# version_1.net
KiCad netlist of a schematic drawn in Altium Designer
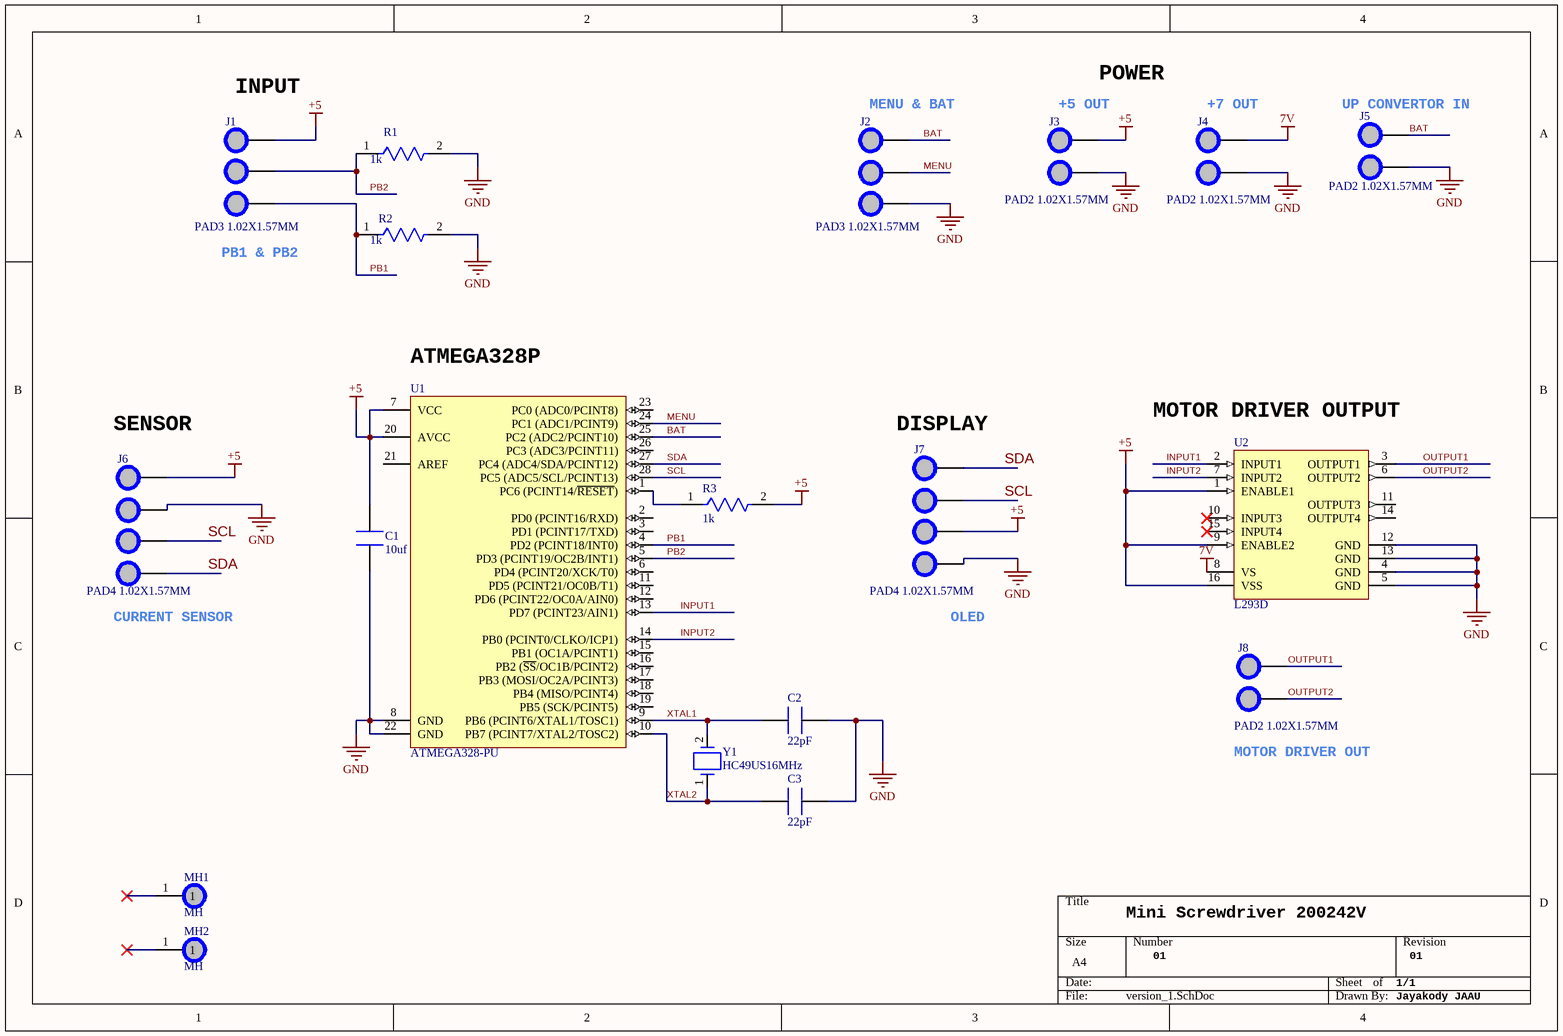
[diagram p0: version_1.SchDoc]

(export (version "E")
  (design (tool "Eeschema 10.0.6"))
  (components
    (comp (ref "C1")
      (value "10uf")
      (footprint "0805 cap")
      (fields
        (field (name "MANUFACTURER") "Samsung")
        (field (name "MANUFACTURER PART NUMBER") "CL21A106KOQNNNE")
        (field (name "TOLERANCE") "10%")
      )
      (libsource (lib "Schlib1") (part "CL21A106KOQNNNE"))
    )
    (comp (ref "C2")
      (value "22pF")
      (footprint "Capacitor_22pF")
      (description "Cap Ceramic Suppression X1/Y2 22pF 760VAC/500VAC U2J 10% (8 X 5mm) Radial 10mm 125C Bulk")
      (fields
        (field (name "MANUFACTURER") "Vishay BCcomponents")
        (field (name "MANUFACTURER PART NUMBER") "VY1220K31U2JQ63V0")
      )
      (libsource (lib "Schlib1") (part "VY1220K31U2JQ63V0"))
    )
    (comp (ref "C3")
      (value "22pF")
      (footprint "Capacitor_22pF")
      (description "Cap Ceramic Suppression X1/Y2 22pF 760VAC/500VAC U2J 10% (8 X 5mm) Radial 10mm 125C Bulk")
      (fields
        (field (name "MANUFACTURER") "Vishay BCcomponents")
        (field (name "MANUFACTURER PART NUMBER") "VY1220K31U2JQ63V0")
      )
      (libsource (lib "Schlib1") (part "VY1220K31U2JQ63V0"))
    )
    (comp (ref "J1")
      (value "PAD3 1.02X1.57MM")
      (footprint "PAD3 1.02X1.57MM")
      (libsource (lib "Schlib1") (part "PAD3 1.02X1.57MM"))
    )
    (comp (ref "J2")
      (value "PAD3 1.02X1.57MM")
      (footprint "PAD3 1.02X1.57MM")
      (libsource (lib "Schlib1") (part "PAD3 1.02X1.57MM"))
    )
    (comp (ref "J3")
      (value "PAD2 1.02X1.57MM")
      (footprint "PAD2 1.02X1.57MM")
      (libsource (lib "Schlib1") (part "PAD2 1.02X1.57MM"))
    )
    (comp (ref "J4")
      (value "PAD2 1.02X1.57MM")
      (footprint "PAD2 1.02X1.57MM")
      (libsource (lib "Schlib1") (part "PAD2 1.02X1.57MM"))
    )
    (comp (ref "J5")
      (value "PAD2 1.02X1.57MM")
      (footprint "PAD2 1.02X1.57MM")
      (libsource (lib "Schlib1") (part "PAD2 1.02X1.57MM"))
    )
    (comp (ref "J6")
      (value "PAD4 1.02X1.57MM")
      (footprint "PAD4 1.02X1.57MM")
      (libsource (lib "Schlib1") (part "PAD4 1.02X1.57MM"))
    )
    (comp (ref "J7")
      (value "PAD4 1.02X1.57MM")
      (footprint "PAD4 1.02X1.57MM")
      (libsource (lib "Schlib1") (part "PAD4 1.02X1.57MM"))
    )
    (comp (ref "J8")
      (value "PAD2 1.02X1.57MM")
      (footprint "PAD2 1.02X1.57MM")
      (libsource (lib "Schlib1") (part "PAD2 1.02X1.57MM"))
    )
    (comp (ref "MH1") (value "MH") (footprint "MH") (libsource (lib "Schlib1") (part "MH")))
    (comp (ref "MH2") (value "MH") (footprint "MH") (libsource (lib "Schlib1") (part "MH")))
    (comp (ref "R1")
      (value "1k")
      (footprint "resistor")
      (description "MRS25 Series Axial Thin Film Resistor 1kOhms +/-1% 0.6W +/-50ppm/degC")
      (fields
        (field (name "MANUFACTURER") "Vishay")
        (field (name "MANUFACTURER PART NUMBER") "MRS25000C1001FCT00")
      )
      (libsource (lib "Schlib1") (part "MRS25000C1001FCT00"))
    )
    (comp (ref "R2")
      (value "1k")
      (footprint "resistor")
      (description "MRS25 Series Axial Thin Film Resistor 1kOhms +/-1% 0.6W +/-50ppm/degC")
      (fields
        (field (name "MANUFACTURER") "Vishay")
        (field (name "MANUFACTURER PART NUMBER") "MRS25000C1001FCT00")
      )
      (libsource (lib "Schlib1") (part "MRS25000C1001FCT00"))
    )
    (comp (ref "R3")
      (value "1k")
      (footprint "resistor")
      (description "MRS25 Series Axial Thin Film Resistor 1kOhms +/-1% 0.6W +/-50ppm/degC")
      (fields
        (field (name "MANUFACTURER") "Vishay")
        (field (name "MANUFACTURER PART NUMBER") "MRS25000C1001FCT00")
      )
      (libsource (lib "Schlib1") (part "MRS25000C1001FCT00"))
    )
    (comp (ref "U1")
      (value "ATMEGA328-PU")
      (footprint "DIP28 7.62MM")
      (description "ATmega Series 32 kB Flash 2 kB SRAM 20 MHz 8-Bit Microcontroller - DIP-28")
      (fields (field (name "MANUFACTURER") "Microchip"))
      (libsource (lib "Schlib1") (part "ATMEGA328-PU"))
    )
    (comp (ref "U2")
      (value "L293D")
      (footprint "DIP16")
      (description "IC MOTOR DRIVER PAR 16-DIP")
      (fields (field (name "MANUFACTURER") "STMicroelectronics"))
      (libsource (lib "Schlib1") (part "L293D"))
    )
    (comp (ref "Y1")
      (value "HC49US16MHz")
      (footprint "HC49US16MHz")
      (fields
        (field (name "MANUFACTURER") "Citizen")
        (field (name "MANUFACTURER PART NUMBER") "HC49US16.384MABJ-UB")
      )
      (libsource (lib "Schlib1") (part "HC49US16.384MABJ-UB"))
    )
  )
  (nets
    (net (code "1") (name "+5") (class "Default")
      (node (ref "C1") (pin "2") (pinfunction "2_2") (pintype "passive"))
      (node (ref "J1") (pin "3") (pinfunction "3_3") (pintype "passive"))
      (node (ref "J3") (pin "1") (pinfunction "1_1") (pintype "passive"))
      (node (ref "J6") (pin "4") (pinfunction "4_4") (pintype "passive"))
      (node (ref "J7") (pin "3") (pinfunction "3_3") (pintype "passive"))
      (node (ref "R3") (pin "2") (pinfunction "2_2") (pintype "passive"))
      (node (ref "U1") (pin "20") (pinfunction "AVCC_20") (pintype "power_in"))
      (node (ref "U1") (pin "7") (pinfunction "VCC_7") (pintype "power_in"))
      (node (ref "U2") (pin "1") (pinfunction "ENABLE1_1") (pintype "input"))
      (node (ref "U2") (pin "16") (pinfunction "VSS_16") (pintype "passive"))
      (node (ref "U2") (pin "9") (pinfunction "ENABLE2_9") (pintype "input"))
    )
    (net (code "2") (name "/BAT") (class "Default")
      (node (ref "J2") (pin "1") (pinfunction "1_1") (pintype "passive"))
      (node (ref "J5") (pin "1") (pinfunction "1_1") (pintype "passive"))
      (node (ref "U1") (pin "25") (pinfunction "PC2_(ADC2/PCINT10)_25") (pintype "bidirectional"))
    )
    (net (code "3") (name "/INPUT1") (class "Default")
      (node (ref "U1") (pin "13") (pinfunction "PD7_(PCINT23/AIN1)_13") (pintype "bidirectional"))
      (node (ref "U2") (pin "2") (pinfunction "INPUT1_2") (pintype "input"))
    )
    (net (code "4") (name "/INPUT2") (class "Default")
      (node (ref "U1") (pin "14") (pinfunction "PB0_(PCINT0/CLKO/ICP1)_14") (pintype "bidirectional"))
      (node (ref "U2") (pin "7") (pinfunction "INPUT2_7") (pintype "input"))
    )
    (net (code "5") (name "/MENU") (class "Default")
      (node (ref "J2") (pin "2") (pinfunction "2_2") (pintype "passive"))
      (node (ref "U1") (pin "24") (pinfunction "PC1_(ADC1/PCINT9)_24") (pintype "bidirectional"))
    )
    (net (code "6") (name "/OUTPUT1") (class "Default")
      (node (ref "J8") (pin "1") (pinfunction "1_1") (pintype "passive"))
      (node (ref "U2") (pin "3") (pinfunction "OUTPUT1_3") (pintype "output"))
    )
    (net (code "7") (name "/OUTPUT2") (class "Default")
      (node (ref "J8") (pin "2") (pinfunction "2_2") (pintype "passive"))
      (node (ref "U2") (pin "6") (pinfunction "OUTPUT2_6") (pintype "output"))
    )
    (net (code "8") (name "/PB1") (class "Default")
      (node (ref "J1") (pin "1") (pinfunction "1_1") (pintype "passive"))
      (node (ref "R2") (pin "1") (pinfunction "1_1") (pintype "passive"))
      (node (ref "U1") (pin "4") (pinfunction "PD2_(PCINT18/INT0)_4") (pintype "bidirectional"))
    )
    (net (code "9") (name "/PB2") (class "Default")
      (node (ref "J1") (pin "2") (pinfunction "2_2") (pintype "passive"))
      (node (ref "R1") (pin "1") (pinfunction "1_1") (pintype "passive"))
      (node (ref "U1") (pin "5") (pinfunction "PD3_(PCINT19/OC2B/INT1)_5") (pintype "bidirectional"))
    )
    (net (code "10") (name "/SCL") (class "Default")
      (node (ref "J6") (pin "2") (pinfunction "2_2") (pintype "passive"))
      (node (ref "J7") (pin "2") (pinfunction "2_2") (pintype "passive"))
      (node (ref "U1") (pin "28") (pinfunction "PC5_(ADC5/SCL/PCINT13)_28") (pintype "bidirectional"))
    )
    (net (code "11") (name "/SDA") (class "Default")
      (node (ref "J6") (pin "1") (pinfunction "1_1") (pintype "passive"))
      (node (ref "J7") (pin "1") (pinfunction "1_1") (pintype "passive"))
      (node (ref "U1") (pin "27") (pinfunction "PC4_(ADC4/SDA/PCINT12)_27") (pintype "bidirectional"))
    )
    (net (code "12") (name "/XTAL1") (class "Default")
      (node (ref "C2") (pin "1") (pinfunction "1_1") (pintype "passive"))
      (node (ref "U1") (pin "9") (pinfunction "PB6_(PCINT6/XTAL1/TOSC1)_9") (pintype "bidirectional"))
      (node (ref "Y1") (pin "2") (pinfunction "2_2") (pintype "passive"))
    )
    (net (code "13") (name "/XTAL2") (class "Default")
      (node (ref "C3") (pin "1") (pinfunction "1_1") (pintype "passive"))
      (node (ref "U1") (pin "10") (pinfunction "PB7_(PCINT7/XTAL2/TOSC2)_10") (pintype "bidirectional"))
      (node (ref "Y1") (pin "1") (pinfunction "1_1") (pintype "passive"))
    )
    (net (code "14") (name "7V") (class "Default")
      (node (ref "J4") (pin "1") (pinfunction "1_1") (pintype "passive"))
      (node (ref "U2") (pin "8") (pinfunction "VS_8") (pintype "passive"))
    )
    (net (code "15") (name "GND") (class "Default")
      (node (ref "C1") (pin "1") (pinfunction "1_1") (pintype "passive"))
      (node (ref "C2") (pin "2") (pinfunction "2_2") (pintype "passive"))
      (node (ref "C3") (pin "2") (pinfunction "2_2") (pintype "passive"))
      (node (ref "J2") (pin "3") (pinfunction "3_3") (pintype "passive"))
      (node (ref "J3") (pin "2") (pinfunction "2_2") (pintype "passive"))
      (node (ref "J4") (pin "2") (pinfunction "2_2") (pintype "passive"))
      (node (ref "J5") (pin "2") (pinfunction "2_2") (pintype "passive"))
      (node (ref "J6") (pin "3") (pinfunction "3_3") (pintype "passive"))
      (node (ref "J7") (pin "4") (pinfunction "4_4") (pintype "passive"))
      (node (ref "R1") (pin "2") (pinfunction "2_2") (pintype "passive"))
      (node (ref "R2") (pin "2") (pinfunction "2_2") (pintype "passive"))
      (node (ref "U1") (pin "22") (pinfunction "GND_22") (pintype "power_in"))
      (node (ref "U1") (pin "8") (pinfunction "GND_8") (pintype "power_in"))
      (node (ref "U2") (pin "12") (pinfunction "GND_12") (pintype "passive"))
      (node (ref "U2") (pin "13") (pinfunction "GND_13") (pintype "passive"))
      (node (ref "U2") (pin "4") (pinfunction "GND_4") (pintype "passive"))
      (node (ref "U2") (pin "5") (pinfunction "GND_5") (pintype "passive"))
    )
    (net (code "16") (name "Net-(U1-PC6_(PCINT14{slash}~{RESET}))") (class "Default")
      (node (ref "R3") (pin "1") (pinfunction "1_1") (pintype "passive"))
      (node (ref "U1") (pin "1") (pinfunction "PC6_(PCINT14/~{RESET})_1") (pintype "bidirectional"))
    )
    (net (code "17") (name "unconnected-(MH1-Pad1)") (class "Default")
      (node (ref "MH1") (pin "1") (pinfunction "1_1") (pintype "passive+no_connect"))
    )
    (net (code "18") (name "unconnected-(MH2-Pad1)") (class "Default")
      (node (ref "MH2") (pin "1") (pinfunction "1_1") (pintype "passive+no_connect"))
    )
    (net (code "19") (name "unconnected-(U1-AREF-Pad21)") (class "Default")
      (node (ref "U1") (pin "21") (pinfunction "AREF_21") (pintype "power_in"))
    )
    (net (code "20") (name "unconnected-(U1-PB1_(OC1A{slash}PCINT1)-Pad15)") (class "Default")
      (node (ref "U1") (pin "15") (pinfunction "PB1_(OC1A/PCINT1)_15") (pintype "bidirectional"))
    )
    (net (code "21") (name "unconnected-(U1-PB2_(~{SS}{slash}OC1B{slash}PCINT2)-Pad16)") (class "Default")
      (node (ref "U1") (pin "16") (pinfunction "PB2_(~{SS}/OC1B/PCINT2)_16") (pintype "bidirectional"))
    )
    (net (code "22") (name "unconnected-(U1-PB3_(MOSI{slash}OC2A{slash}PCINT3)-Pad17)") (class "Default")
      (node (ref "U1") (pin "17") (pinfunction "PB3_(MOSI/OC2A/PCINT3)_17") (pintype "bidirectional"))
    )
    (net (code "23") (name "unconnected-(U1-PB4_(MISO{slash}PCINT4)-Pad18)") (class "Default")
      (node (ref "U1") (pin "18") (pinfunction "PB4_(MISO/PCINT4)_18") (pintype "bidirectional"))
    )
    (net (code "24") (name "unconnected-(U1-PB5_(SCK{slash}PCINT5)-Pad19)") (class "Default")
      (node (ref "U1") (pin "19") (pinfunction "PB5_(SCK/PCINT5)_19") (pintype "bidirectional"))
    )
    (net (code "25") (name "unconnected-(U1-PC0_(ADC0{slash}PCINT8)-Pad23)") (class "Default")
      (node (ref "U1") (pin "23") (pinfunction "PC0_(ADC0/PCINT8)_23") (pintype "bidirectional"))
    )
    (net (code "26") (name "unconnected-(U1-PC3_(ADC3{slash}PCINT11)-Pad26)") (class "Default")
      (node (ref "U1") (pin "26") (pinfunction "PC3_(ADC3/PCINT11)_26") (pintype "bidirectional"))
    )
    (net (code "27") (name "unconnected-(U1-PD0_(PCINT16{slash}RXD)-Pad2)") (class "Default")
      (node (ref "U1") (pin "2") (pinfunction "PD0_(PCINT16/RXD)_2") (pintype "bidirectional"))
    )
    (net (code "28") (name "unconnected-(U1-PD1_(PCINT17{slash}TXD)-Pad3)") (class "Default")
      (node (ref "U1") (pin "3") (pinfunction "PD1_(PCINT17/TXD)_3") (pintype "bidirectional"))
    )
    (net (code "29") (name "unconnected-(U1-PD4_(PCINT20{slash}XCK{slash}T0)-Pad6)") (class "Default")
      (node (ref "U1") (pin "6") (pinfunction "PD4_(PCINT20/XCK/T0)_6") (pintype "bidirectional"))
    )
    (net (code "30") (name "unconnected-(U1-PD5_(PCINT21{slash}OC0B{slash}T1)-Pad11)") (class "Default")
      (node (ref "U1") (pin "11") (pinfunction "PD5_(PCINT21/OC0B/T1)_11") (pintype "bidirectional"))
    )
    (net (code "31") (name "unconnected-(U1-PD6_(PCINT22{slash}OC0A{slash}AIN0)-Pad12)") (class "Default")
      (node (ref "U1") (pin "12") (pinfunction "PD6_(PCINT22/OC0A/AIN0)_12") (pintype "bidirectional"))
    )
    (net (code "32") (name "unconnected-(U2-INPUT3-Pad10)") (class "Default")
      (node (ref "U2") (pin "10") (pinfunction "INPUT3_10") (pintype "input+no_connect"))
    )
    (net (code "33") (name "unconnected-(U2-INPUT4-Pad15)") (class "Default")
      (node (ref "U2") (pin "15") (pinfunction "INPUT4_15") (pintype "input+no_connect"))
    )
    (net (code "34") (name "unconnected-(U2-OUTPUT3-Pad11)") (class "Default")
      (node (ref "U2") (pin "11") (pinfunction "OUTPUT3_11") (pintype "output"))
    )
    (net (code "35") (name "unconnected-(U2-OUTPUT4-Pad14)") (class "Default")
      (node (ref "U2") (pin "14") (pinfunction "OUTPUT4_14") (pintype "output"))
    )
  )
)
